# Sheet1.net
KiCad netlist of a schematic drawn in Altium Designer
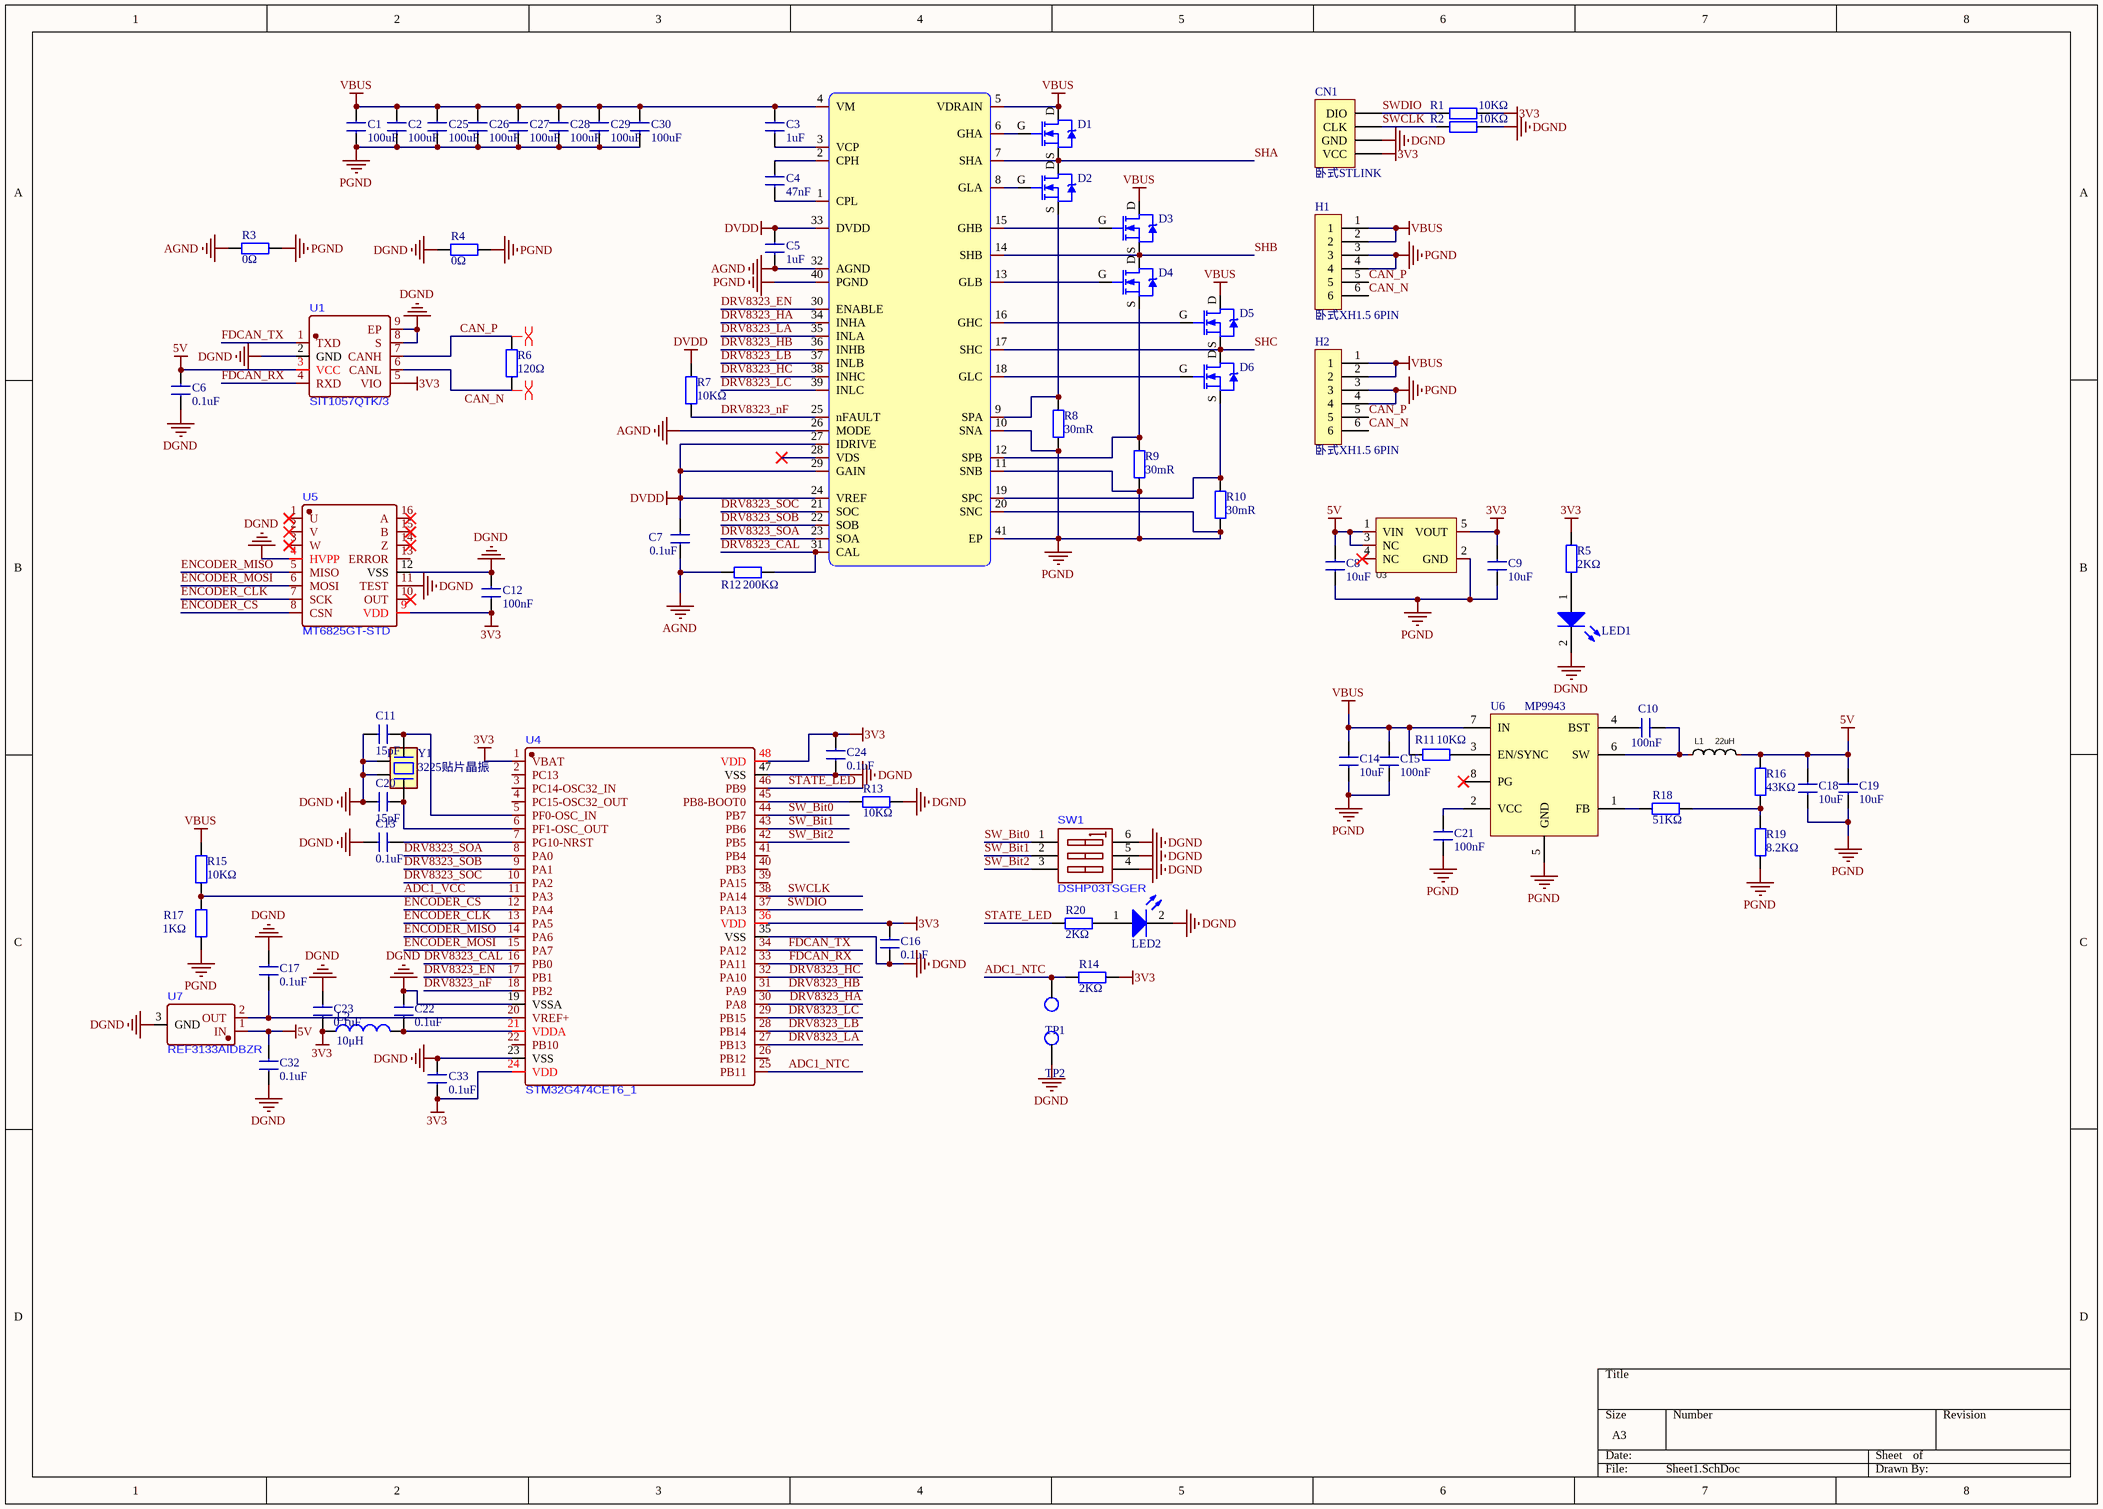
[diagram p0: Sheet1.SchDoc]

(export (version "E")
  (design (tool "Eeschema 10.0.6"))
  (components
    (comp (ref "C1")
      (value "100uF")
      (footprint "1206")
      (description "1210贴片电容")
      (libsource (lib "Integrated_Library1") (part "1210贴片电容"))
    )
    (comp (ref "C2")
      (value "100uF")
      (footprint "1206")
      (description "1210贴片电容")
      (libsource (lib "Integrated_Library1") (part "1210贴片电容"))
    )
    (comp (ref "C3")
      (value "1uF")
      (footprint "c0402")
      (description "贴片电容0402")
      (libsource (lib "Integrated_Library1") (part "0402贴片电容"))
    )
    (comp (ref "C4")
      (value "47nF")
      (footprint "c0402")
      (description "贴片电容0402")
      (libsource (lib "Integrated_Library1") (part "0402贴片电容"))
    )
    (comp (ref "C5")
      (value "1uF")
      (footprint "c0402")
      (description "贴片电容0402")
      (libsource (lib "Integrated_Library1") (part "0402贴片电容"))
    )
    (comp (ref "C6")
      (value "0.1uF")
      (footprint "c0402")
      (description "贴片电容0402")
      (libsource (lib "Integrated_Library1") (part "0402贴片电容"))
    )
    (comp (ref "C7")
      (value "0.1uF")
      (footprint "c0402")
      (description "贴片电容0402")
      (libsource (lib "Integrated_Library1") (part "0402贴片电容"))
    )
    (comp (ref "C8")
      (value "10uF")
      (footprint "c0402")
      (description "贴片电容0402")
      (libsource (lib "Integrated_Library1") (part "0402贴片电容"))
    )
    (comp (ref "C9")
      (value "10uF")
      (footprint "c0402")
      (description "贴片电容0402")
      (libsource (lib "Integrated_Library1") (part "0402贴片电容"))
    )
    (comp (ref "C10")
      (value "100nF")
      (footprint "c0402")
      (description "贴片电容0402")
      (libsource (lib "Integrated_Library1") (part "0402贴片电容"))
    )
    (comp (ref "C11")
      (value "15pF")
      (footprint "c0402")
      (description "贴片电容0402")
      (libsource (lib "Integrated_Library1") (part "0402贴片电容"))
    )
    (comp (ref "C12")
      (value "100nF")
      (footprint "C0402")
      (description "贴片电容0402")
      (libsource (lib "Integrated_Library1") (part "0402贴片电容"))
    )
    (comp (ref "C13")
      (value "0.1uF")
      (footprint "c0402")
      (description "贴片电容0402")
      (libsource (lib "Integrated_Library1") (part "0402贴片电容"))
    )
    (comp (ref "C14")
      (value "10uF")
      (footprint "C0603")
      (description "1210贴片电容")
      (libsource (lib "Integrated_Library1") (part "1210贴片电容"))
    )
    (comp (ref "C15")
      (value "100nF")
      (footprint "c0402")
      (description "贴片电容0402")
      (libsource (lib "Integrated_Library1") (part "0402贴片电容"))
    )
    (comp (ref "C16")
      (value "0.1uF")
      (footprint "c0402")
      (description "贴片电容0402")
      (libsource (lib "Integrated_Library1") (part "0402贴片电容"))
    )
    (comp (ref "C17")
      (value "0.1uF")
      (footprint "c0402")
      (description "贴片电容0402")
      (libsource (lib "Integrated_Library1") (part "0402贴片电容"))
    )
    (comp (ref "C18")
      (value "10uF")
      (footprint "C0603")
      (description "1210贴片电容")
      (libsource (lib "Integrated_Library1") (part "1210贴片电容"))
    )
    (comp (ref "C19")
      (value "10uF")
      (footprint "C0603")
      (description "1210贴片电容")
      (libsource (lib "Integrated_Library1") (part "1210贴片电容"))
    )
    (comp (ref "C20")
      (value "15pF")
      (footprint "c0402")
      (description "贴片电容0402")
      (libsource (lib "Integrated_Library1") (part "0402贴片电容"))
    )
    (comp (ref "C21")
      (value "100nF")
      (footprint "c0402")
      (description "贴片电容0402")
      (libsource (lib "Integrated_Library1") (part "0402贴片电容"))
    )
    (comp (ref "C22")
      (value "0.1uF")
      (footprint "c0402")
      (description "贴片电容0402")
      (libsource (lib "Integrated_Library1") (part "0402贴片电容"))
    )
    (comp (ref "C23")
      (value "0.1uF")
      (footprint "c0402")
      (description "贴片电容0402")
      (libsource (lib "Integrated_Library1") (part "0402贴片电容"))
    )
    (comp (ref "C24")
      (value "0.1uF")
      (footprint "c0402")
      (description "贴片电容0402")
      (libsource (lib "Integrated_Library1") (part "0402贴片电容"))
    )
    (comp (ref "C25")
      (value "100uF")
      (footprint "1206")
      (description "1210贴片电容")
      (libsource (lib "Integrated_Library1") (part "1210贴片电容"))
    )
    (comp (ref "C26")
      (value "100uF")
      (footprint "1206")
      (description "1210贴片电容")
      (libsource (lib "Integrated_Library1") (part "1210贴片电容"))
    )
    (comp (ref "C27")
      (value "100uF")
      (footprint "1206")
      (description "1210贴片电容")
      (libsource (lib "Integrated_Library1") (part "1210贴片电容"))
    )
    (comp (ref "C28")
      (value "100uF")
      (footprint "1206")
      (description "1210贴片电容")
      (libsource (lib "Integrated_Library1") (part "1210贴片电容"))
    )
    (comp (ref "C29")
      (value "100uF")
      (footprint "1206")
      (description "1210贴片电容")
      (libsource (lib "Integrated_Library1") (part "1210贴片电容"))
    )
    (comp (ref "C30")
      (value "100uF")
      (footprint "1206")
      (description "1210贴片电容")
      (libsource (lib "Integrated_Library1") (part "1210贴片电容"))
    )
    (comp (ref "C32")
      (value "0.1uF")
      (footprint "c0402")
      (description "贴片电容0402")
      (libsource (lib "Integrated_Library1") (part "0402贴片电容"))
    )
    (comp (ref "C33")
      (value "0.1uF")
      (footprint "c0402")
      (description "贴片电容0402")
      (libsource (lib "Integrated_Library1") (part "0402贴片电容"))
    )
    (comp (ref "CN1")
      (value "卧式STLINK")
      (footprint "CONN-SMD_4P-P1.25_GH1.25-4P")
      (libsource (lib "Integrated_Library1") (part "卧式STLINK"))
    )
    (comp (ref "D1")
      (value "NTMFS5C410NL")
      (footprint "DFN-8_L3.0-W3.0-P0.65-BL")
      (description "N沟道MOS管")
      (fields (field (name "PUBLISHER") "Altium Limited"))
      (libsource (lib "En") (part "NTMFS5C410NL"))
    )
    (comp (ref "D2")
      (value "NTMFS5C410NL")
      (footprint "DFN-8_L3.0-W3.0-P0.65-BL")
      (description "N沟道MOS管")
      (fields (field (name "PUBLISHER") "Altium Limited"))
      (libsource (lib "En") (part "NTMFS5C410NL"))
    )
    (comp (ref "D3")
      (value "NTMFS5C410NL")
      (footprint "DFN-8_L3.0-W3.0-P0.65-BL")
      (description "N沟道MOS管")
      (fields (field (name "PUBLISHER") "Altium Limited"))
      (libsource (lib "En") (part "NTMFS5C410NL"))
    )
    (comp (ref "D4")
      (value "NTMFS5C410NL")
      (footprint "DFN-8_L3.0-W3.0-P0.65-BL")
      (description "N沟道MOS管")
      (fields (field (name "PUBLISHER") "Altium Limited"))
      (libsource (lib "En") (part "NTMFS5C410NL"))
    )
    (comp (ref "D5")
      (value "NTMFS5C410NL")
      (footprint "DFN-8_L3.0-W3.0-P0.65-BL")
      (description "N沟道MOS管")
      (fields (field (name "PUBLISHER") "Altium Limited"))
      (libsource (lib "En") (part "NTMFS5C410NL"))
    )
    (comp (ref "D6")
      (value "NTMFS5C410NL")
      (footprint "DFN-8_L3.0-W3.0-P0.65-BL")
      (description "N沟道MOS管")
      (fields (field (name "PUBLISHER") "Altium Limited"))
      (libsource (lib "En") (part "NTMFS5C410NL"))
    )
    (comp (ref "H1")
      (value "卧式XH1.5 6PIN")
      (footprint "CONN-SMD_6P-P1.50_ZX-ZH1.5-6PWT")
      (libsource (lib "En") (part "卧式XH1.5 6PIN"))
    )
    (comp (ref "H2")
      (value "卧式XH1.5 6PIN")
      (footprint "CONN-SMD_6P-P1.50_ZX-ZH1.5-6PWT")
      (libsource (lib "En") (part "卧式XH1.5 6PIN"))
    )
    (comp (ref "L1")
      (value "22uH")
      (footprint "IND-SMD_L2.5-W2.0")
      (description "一体成型屏蔽电感，0530封装，额定电流3A")
      (fields (field (name "MANUFACTURER") "XR(祥如)") (field (name "MANUFACTURER PART") "XR0530-100M"))
      (libsource (lib "Integrated_Library1") (part "0530屏蔽电感"))
    )
    (comp (ref "L2")
      (value "10μH")
      (footprint "L0805")
      (description "0805贴片电感")
      (libsource (lib "Integrated_Library1") (part "0805贴片电感"))
    )
    (comp (ref "LED1")
      (value "LED")
      (footprint "led0805")
      (description "0805贴片LED")
      (libsource (lib "Integrated_Library1") (part "0805贴片LED"))
    )
    (comp (ref "LED2")
      (value "LED")
      (footprint "led0805")
      (description "0805贴片LED")
      (libsource (lib "Integrated_Library1") (part "0805贴片LED"))
    )
    (comp (ref "R1")
      (value "10KΩ")
      (footprint "R0402")
      (description "0402贴片电阻")
      (libsource (lib "") (part "0402贴片电阻_3"))
    )
    (comp (ref "R2")
      (value "10KΩ")
      (footprint "R0402")
      (description "0402贴片电阻")
      (libsource (lib "") (part "0402贴片电阻_3"))
    )
    (comp (ref "R3")
      (value "0Ω")
      (footprint "R0402")
      (description "0402贴片电阻")
      (libsource (lib "") (part "0402贴片电阻_3"))
    )
    (comp (ref "R4")
      (value "0Ω")
      (footprint "R0402")
      (description "0402贴片电阻")
      (libsource (lib "") (part "0402贴片电阻_3"))
    )
    (comp (ref "R5")
      (value "2KΩ")
      (footprint "R0402")
      (description "0402贴片电阻")
      (libsource (lib "") (part "0402贴片电阻_2"))
    )
    (comp (ref "R6")
      (value "120Ω")
      (footprint "R0402")
      (description "0402贴片电阻")
      (libsource (lib "") (part "0402贴片电阻_1"))
    )
    (comp (ref "R7")
      (value "10KΩ")
      (footprint "R0402")
      (description "0402贴片电阻")
      (libsource (lib "") (part "0402贴片电阻_2"))
    )
    (comp (ref "R8")
      (value "30mR")
      (footprint "1206")
      (description "2512检流电阻")
      (libsource (lib "Integrated_Library1") (part "2512检流电阻"))
    )
    (comp (ref "R9")
      (value "30mR")
      (footprint "1206")
      (description "2512检流电阻")
      (libsource (lib "Integrated_Library1") (part "2512检流电阻"))
    )
    (comp (ref "R10")
      (value "30mR")
      (footprint "1206")
      (description "2512检流电阻")
      (libsource (lib "Integrated_Library1") (part "2512检流电阻"))
    )
    (comp (ref "R11")
      (value "10KΩ")
      (footprint "R0402")
      (description "0402贴片电阻")
      (libsource (lib "Integrated_Library1") (part "0402贴片电阻"))
    )
    (comp (ref "R12")
      (value "200KΩ")
      (footprint "R0402")
      (description "0402贴片电阻")
      (libsource (lib "") (part "0402贴片电阻_5"))
    )
    (comp (ref "R13")
      (value "10KΩ")
      (footprint "R0402")
      (description "0402贴片电阻")
      (libsource (lib "") (part "0402贴片电阻_3"))
    )
    (comp (ref "R14")
      (value "2KΩ")
      (footprint "R0402")
      (description "0402贴片电阻")
      (libsource (lib "") (part "0402贴片电阻_3"))
    )
    (comp (ref "R15")
      (value "10KΩ")
      (footprint "R0402")
      (description "0402贴片电阻")
      (libsource (lib "") (part "0402贴片电阻_1"))
    )
    (comp (ref "R16")
      (value "43KΩ")
      (footprint "R0402")
      (description "0402贴片电阻")
      (libsource (lib "") (part "0402贴片电阻_4"))
    )
    (comp (ref "R17")
      (value "1KΩ")
      (footprint "R0402")
      (description "0402贴片电阻")
      (libsource (lib "") (part "0402贴片电阻_2"))
    )
    (comp (ref "R18")
      (value "51KΩ")
      (footprint "R0402")
      (description "0402贴片电阻")
      (libsource (lib "Integrated_Library1") (part "0402贴片电阻"))
    )
    (comp (ref "R19")
      (value "8.2KΩ")
      (footprint "R0402")
      (description "0402贴片电阻")
      (libsource (lib "") (part "0402贴片电阻_4"))
    )
    (comp (ref "R20")
      (value "2KΩ")
      (footprint "R0402")
      (description "0402贴片电阻")
      (libsource (lib "") (part "0402贴片电阻_3"))
    )
    (comp (ref "SW1")
      (value "DSHP03TSGER")
      (footprint "SW-SMD_6P-L5.4-W5.4-P1.27-LS8.4")
      (libsource (lib "Integrated_Library1") (part "DSHP03TSGER"))
    )
    (comp (ref "TP1")
      (value "testpoint")
      (footprint "testpoint")
      (libsource (lib "Integrated_Library1") (part "testpoint"))
    )
    (comp (ref "TP2")
      (value "testpoint")
      (footprint "testpoint")
      (libsource (lib "Integrated_Library1") (part "testpoint"))
    )
    (comp (ref "U1")
      (value "SIT1057QTK/3")
      (footprint "DFN-8_L3.0-W3.0-P0.65-BL-EP")
      (libsource (lib "En") (part "SIT1057QTK/3"))
    )
    (comp (ref "U2")
      (value "DRV8323HRTAR")
      (footprint "QFN-40_L6.0-W6.0-P0.50-BL-EP4.5")
      (fields (field (name "MANUFACTURER") "TI(德州仪器)"))
      (libsource (lib "Integrated_Library1") (part "DRV8323HRTAR"))
    )
    (comp (ref "U3")
      (value "XC6201P332MR-HXY")
      (footprint "SOT-23-5_L3.0-W1.7-P0.95-LS2.8-BR")
      (description "3.3V LDO")
      (fields (field (name "MANUFACTURER") "HXY MOSFET(华轩阳电子)"))
      (libsource (lib "Integrated_Library1") (part "XC6201P332MR-HXY"))
    )
    (comp (ref "U4")
      (value "STM32G474CET6_1")
      (footprint "LQFP-48_L7.0-W7.0-P0.50-LS9.0-BL")
      (libsource (lib "Integrated_Library1") (part "STM32G474CET6_1"))
    )
    (comp (ref "U5")
      (value "MT6825GT-STD")
      (footprint "TSSOP-16_L5.0-W4.4-P0.65-LS6.4-BL-1")
      (description "18位绝对角编码器")
      (libsource (lib "Integrated_Library1") (part "MT6825GT-STD"))
    )
    (comp (ref "U6")
      (value "MP9943")
      (footprint "QFN-8 3x3")
      (libsource (lib "Integrated_Library1") (part "MP9943"))
    )
    (comp (ref "U7")
      (value "REF3133AIDBZR")
      (footprint "SOT-23-3_L2.9-W1.3-P1.90-LS2.4-BR")
      (libsource (lib "Integrated_Library1") (part "REF3133AIDBZR"))
    )
    (comp (ref "Y1")
      (value "3225贴片晶振")
      (footprint "OSC-3225-4P")
      (libsource (lib "Integrated_Library1") (part "3225贴片晶振"))
    )
  )
  (nets
    (net (code "1") (name "/ADC1_NTC") (class "Default")
      (node (ref "R14") (pin "1") (pinfunction "1_1") (pintype "passive"))
      (node (ref "TP1") (pin "1") (pinfunction "1_1") (pintype "passive"))
      (node (ref "U4") (pin "25") (pinfunction "PB11_25") (pintype "passive"))
    )
    (net (code "2") (name "/ADC1_VCC") (class "Default")
      (node (ref "R15") (pin "1") (pinfunction "1_1") (pintype "passive"))
      (node (ref "R17") (pin "1") (pinfunction "1_1") (pintype "passive"))
      (node (ref "U4") (pin "11") (pinfunction "PA3_11") (pintype "passive"))
    )
    (net (code "3") (name "/CAN_N") (class "Default")
      (node (ref "H1") (pin "6") (pinfunction "6_6") (pintype "passive"))
      (node (ref "H2") (pin "6") (pinfunction "6_6") (pintype "passive"))
      (node (ref "R6") (pin "1") (pinfunction "1_1") (pintype "passive"))
      (node (ref "U1") (pin "6") (pinfunction "CANL_6") (pintype "passive"))
    )
    (net (code "4") (name "/CAN_P") (class "Default")
      (node (ref "H1") (pin "5") (pinfunction "5_5") (pintype "passive"))
      (node (ref "H2") (pin "5") (pinfunction "5_5") (pintype "passive"))
      (node (ref "R6") (pin "2") (pinfunction "2_2") (pintype "passive"))
      (node (ref "U1") (pin "7") (pinfunction "CANH_7") (pintype "passive"))
    )
    (net (code "5") (name "/DRV8323_CAL") (class "Default")
      (node (ref "R12") (pin "1") (pinfunction "1_1") (pintype "passive"))
      (node (ref "U2") (pin "31") (pinfunction "CAL_31") (pintype "passive"))
      (node (ref "U4") (pin "16") (pinfunction "PB0_16") (pintype "passive"))
    )
    (net (code "6") (name "/DRV8323_EN") (class "Default")
      (node (ref "U2") (pin "30") (pinfunction "ENABLE_30") (pintype "passive"))
      (node (ref "U4") (pin "17") (pinfunction "PB1_17") (pintype "passive"))
    )
    (net (code "7") (name "/DRV8323_HA") (class "Default")
      (node (ref "U2") (pin "34") (pinfunction "INHA_34") (pintype "passive"))
      (node (ref "U4") (pin "30") (pinfunction "PA8_30") (pintype "passive"))
    )
    (net (code "8") (name "/DRV8323_HB") (class "Default")
      (node (ref "U2") (pin "36") (pinfunction "INHB_36") (pintype "passive"))
      (node (ref "U4") (pin "31") (pinfunction "PA9_31") (pintype "passive"))
    )
    (net (code "9") (name "/DRV8323_HC") (class "Default")
      (node (ref "U2") (pin "38") (pinfunction "INHC_38") (pintype "passive"))
      (node (ref "U4") (pin "32") (pinfunction "PA10_32") (pintype "passive"))
    )
    (net (code "10") (name "/DRV8323_LA") (class "Default")
      (node (ref "U2") (pin "35") (pinfunction "INLA_35") (pintype "passive"))
      (node (ref "U4") (pin "27") (pinfunction "PB13_27") (pintype "passive"))
    )
    (net (code "11") (name "/DRV8323_LB") (class "Default")
      (node (ref "U2") (pin "37") (pinfunction "INLB_37") (pintype "passive"))
      (node (ref "U4") (pin "28") (pinfunction "PB14_28") (pintype "passive"))
    )
    (net (code "12") (name "/DRV8323_LC") (class "Default")
      (node (ref "U2") (pin "39") (pinfunction "INLC_39") (pintype "passive"))
      (node (ref "U4") (pin "29") (pinfunction "PB15_29") (pintype "passive"))
    )
    (net (code "13") (name "/DRV8323_SOA") (class "Default")
      (node (ref "U2") (pin "23") (pinfunction "SOA_23") (pintype "passive"))
      (node (ref "U4") (pin "8") (pinfunction "PA0_8") (pintype "passive"))
    )
    (net (code "14") (name "/DRV8323_SOB") (class "Default")
      (node (ref "U2") (pin "22") (pinfunction "SOB_22") (pintype "passive"))
      (node (ref "U4") (pin "9") (pinfunction "PA1_9") (pintype "passive"))
    )
    (net (code "15") (name "/DRV8323_SOC") (class "Default")
      (node (ref "U2") (pin "21") (pinfunction "SOC_21") (pintype "passive"))
      (node (ref "U4") (pin "10") (pinfunction "PA2_10") (pintype "passive"))
    )
    (net (code "16") (name "/DRV8323_nF") (class "Default")
      (node (ref "R7") (pin "2") (pinfunction "2_2") (pintype "passive"))
      (node (ref "U2") (pin "25") (pinfunction "nFAULT_25") (pintype "passive"))
      (node (ref "U4") (pin "18") (pinfunction "PB2_18") (pintype "passive"))
    )
    (net (code "17") (name "/ENCODER_CLK") (class "Default")
      (node (ref "U4") (pin "13") (pinfunction "PA5_13") (pintype "passive"))
      (node (ref "U5") (pin "7") (pinfunction "SCK_7") (pintype "passive"))
    )
    (net (code "18") (name "/ENCODER_CS") (class "Default")
      (node (ref "U4") (pin "12") (pinfunction "PA4_12") (pintype "passive"))
      (node (ref "U5") (pin "8") (pinfunction "CSN_8") (pintype "passive"))
    )
    (net (code "19") (name "/ENCODER_MISO") (class "Default")
      (node (ref "U4") (pin "14") (pinfunction "PA6_14") (pintype "passive"))
      (node (ref "U5") (pin "5") (pinfunction "MISO_5") (pintype "passive"))
    )
    (net (code "20") (name "/ENCODER_MOSI") (class "Default")
      (node (ref "U4") (pin "15") (pinfunction "PA7_15") (pintype "passive"))
      (node (ref "U5") (pin "6") (pinfunction "MOSI_6") (pintype "passive"))
    )
    (net (code "21") (name "/FDCAN_RX") (class "Default")
      (node (ref "U1") (pin "4") (pinfunction "RXD_4") (pintype "passive"))
      (node (ref "U4") (pin "33") (pinfunction "PA11_33") (pintype "passive"))
    )
    (net (code "22") (name "/FDCAN_TX") (class "Default")
      (node (ref "U1") (pin "1") (pinfunction "TXD_1") (pintype "passive"))
      (node (ref "U4") (pin "34") (pinfunction "PA12_34") (pintype "passive"))
    )
    (net (code "23") (name "/SHA") (class "Default")
      (node (ref "D1") (pin "S") (pinfunction "S_S") (pintype "passive"))
      (node (ref "D2") (pin "D") (pinfunction "D_D") (pintype "passive"))
      (node (ref "U2") (pin "7") (pinfunction "SHA_7") (pintype "passive"))
    )
    (net (code "24") (name "/SHB") (class "Default")
      (node (ref "D3") (pin "S") (pinfunction "S_S") (pintype "passive"))
      (node (ref "D4") (pin "D") (pinfunction "D_D") (pintype "passive"))
      (node (ref "U2") (pin "14") (pinfunction "SHB_14") (pintype "passive"))
    )
    (net (code "25") (name "/SHC") (class "Default")
      (node (ref "D5") (pin "S") (pinfunction "S_S") (pintype "passive"))
      (node (ref "D6") (pin "D") (pinfunction "D_D") (pintype "passive"))
      (node (ref "U2") (pin "17") (pinfunction "SHC_17") (pintype "passive"))
    )
    (net (code "26") (name "/STATE_LED") (class "Default")
      (node (ref "R20") (pin "1") (pinfunction "1_1") (pintype "passive"))
      (node (ref "U4") (pin "46") (pinfunction "PB9_46") (pintype "passive"))
    )
    (net (code "27") (name "/SWCLK") (class "Default")
      (node (ref "CN1") (pin "3") (pinfunction "CLK_3") (pintype "passive"))
      (node (ref "R2") (pin "1") (pinfunction "1_1") (pintype "passive"))
      (node (ref "U4") (pin "38") (pinfunction "PA14_38") (pintype "passive"))
    )
    (net (code "28") (name "/SWDIO") (class "Default")
      (node (ref "CN1") (pin "4") (pinfunction "DIO_4") (pintype "passive"))
      (node (ref "R1") (pin "1") (pinfunction "1_1") (pintype "passive"))
      (node (ref "U4") (pin "37") (pinfunction "PA13_37") (pintype "passive"))
    )
    (net (code "29") (name "/SW_Bit0") (class "Default")
      (node (ref "SW1") (pin "1") (pinfunction "A1_1") (pintype "passive"))
      (node (ref "U4") (pin "44") (pinfunction "PB7_44") (pintype "passive"))
    )
    (net (code "30") (name "/SW_Bit1") (class "Default")
      (node (ref "SW1") (pin "2") (pinfunction "A2_2") (pintype "passive"))
      (node (ref "U4") (pin "43") (pinfunction "PB6_43") (pintype "passive"))
    )
    (net (code "31") (name "/SW_Bit2") (class "Default")
      (node (ref "SW1") (pin "3") (pinfunction "A3_3") (pintype "passive"))
      (node (ref "U4") (pin "42") (pinfunction "PB5_42") (pintype "passive"))
    )
    (net (code "32") (name "3V3") (class "Default")
      (node (ref "C12") (pin "1") (pinfunction "1_1") (pintype "passive"))
      (node (ref "C16") (pin "1") (pinfunction "1_1") (pintype "passive"))
      (node (ref "C23") (pin "2") (pinfunction "2_2") (pintype "passive"))
      (node (ref "C24") (pin "1") (pinfunction "1_1") (pintype "passive"))
      (node (ref "C33") (pin "2") (pinfunction "2_2") (pintype "passive"))
      (node (ref "C9") (pin "2") (pinfunction "2_2") (pintype "passive"))
      (node (ref "CN1") (pin "1") (pinfunction "VCC_1") (pintype "passive"))
      (node (ref "L2") (pin "1") (pinfunction "1_1") (pintype "passive"))
      (node (ref "R1") (pin "2") (pinfunction "2_2") (pintype "passive"))
      (node (ref "R14") (pin "2") (pinfunction "2_2") (pintype "passive"))
      (node (ref "R5") (pin "1") (pinfunction "1_1") (pintype "passive"))
      (node (ref "U1") (pin "5") (pinfunction "VIO_5") (pintype "passive"))
      (node (ref "U3") (pin "5") (pinfunction "VOUT_5") (pintype "passive"))
      (node (ref "U4") (pin "1") (pinfunction "VBAT_1") (pintype "passive"))
      (node (ref "U4") (pin "24") (pinfunction "VDD_24") (pintype "passive"))
      (node (ref "U4") (pin "36") (pinfunction "VDD_36") (pintype "passive"))
      (node (ref "U4") (pin "48") (pinfunction "VDD_48") (pintype "passive"))
      (node (ref "U5") (pin "9") (pinfunction "VDD_9") (pintype "passive"))
    )
    (net (code "33") (name "5V") (class "Default")
      (node (ref "C18") (pin "2") (pinfunction "2_2") (pintype "passive"))
      (node (ref "C19") (pin "2") (pinfunction "2_2") (pintype "passive"))
      (node (ref "C32") (pin "1") (pinfunction "1_1") (pintype "passive"))
      (node (ref "C6") (pin "2") (pinfunction "2_2") (pintype "passive"))
      (node (ref "C8") (pin "2") (pinfunction "2_2") (pintype "passive"))
      (node (ref "L1") (pin "2") (pinfunction "2_2") (pintype "passive"))
      (node (ref "R16") (pin "2") (pinfunction "2_2") (pintype "passive"))
      (node (ref "U1") (pin "3") (pinfunction "VCC_3") (pintype "passive"))
      (node (ref "U3") (pin "1") (pinfunction "VIN_1") (pintype "passive"))
      (node (ref "U3") (pin "3") (pinfunction "NC_3") (pintype "passive"))
      (node (ref "U7") (pin "1") (pinfunction "IN_1") (pintype "passive"))
    )
    (net (code "34") (name "AGND") (class "Default")
      (node (ref "C5") (pin "1") (pinfunction "1_1") (pintype "passive"))
      (node (ref "C7") (pin "1") (pinfunction "1_1") (pintype "passive"))
      (node (ref "R12") (pin "2") (pinfunction "2_2") (pintype "passive"))
      (node (ref "R3") (pin "1") (pinfunction "1_1") (pintype "passive"))
      (node (ref "U2") (pin "26") (pinfunction "MODE_26") (pintype "passive"))
      (node (ref "U2") (pin "32") (pinfunction "AGND_32") (pintype "passive"))
    )
    (net (code "35") (name "DGND") (class "Default")
      (node (ref "C11") (pin "2") (pinfunction "2_2") (pintype "passive"))
      (node (ref "C12") (pin "2") (pinfunction "2_2") (pintype "passive"))
      (node (ref "C13") (pin "2") (pinfunction "2_2") (pintype "passive"))
      (node (ref "C16") (pin "2") (pinfunction "2_2") (pintype "passive"))
      (node (ref "C17") (pin "2") (pinfunction "2_2") (pintype "passive"))
      (node (ref "C20") (pin "2") (pinfunction "2_2") (pintype "passive"))
      (node (ref "C22") (pin "1") (pinfunction "1_1") (pintype "passive"))
      (node (ref "C23") (pin "1") (pinfunction "1_1") (pintype "passive"))
      (node (ref "C24") (pin "2") (pinfunction "2_2") (pintype "passive"))
      (node (ref "C32") (pin "2") (pinfunction "2_2") (pintype "passive"))
      (node (ref "C33") (pin "1") (pinfunction "1_1") (pintype "passive"))
      (node (ref "C6") (pin "1") (pinfunction "1_1") (pintype "passive"))
      (node (ref "CN1") (pin "2") (pinfunction "GND_2") (pintype "passive"))
      (node (ref "LED1") (pin "2") (pinfunction "K_2") (pintype "passive"))
      (node (ref "LED2") (pin "2") (pinfunction "K_2") (pintype "passive"))
      (node (ref "R13") (pin "2") (pinfunction "2_2") (pintype "passive"))
      (node (ref "R2") (pin "2") (pinfunction "2_2") (pintype "passive"))
      (node (ref "R4") (pin "1") (pinfunction "1_1") (pintype "passive"))
      (node (ref "SW1") (pin "4") (pinfunction "B3_4") (pintype "passive"))
      (node (ref "SW1") (pin "5") (pinfunction "B2_5") (pintype "passive"))
      (node (ref "SW1") (pin "6") (pinfunction "B1_6") (pintype "passive"))
      (node (ref "TP2") (pin "1") (pinfunction "1_1") (pintype "passive"))
      (node (ref "U1") (pin "2") (pinfunction "GND_2") (pintype "passive"))
      (node (ref "U1") (pin "8") (pinfunction "S_8") (pintype "passive"))
      (node (ref "U1") (pin "9") (pinfunction "EP_9") (pintype "passive"))
      (node (ref "U4") (pin "19") (pinfunction "VSSA_19") (pintype "passive"))
      (node (ref "U4") (pin "23") (pinfunction "VSS_23") (pintype "passive"))
      (node (ref "U4") (pin "35") (pinfunction "VSS_35") (pintype "passive"))
      (node (ref "U4") (pin "47") (pinfunction "VSS_47") (pintype "passive"))
      (node (ref "U5") (pin "11") (pinfunction "TEST_11") (pintype "passive"))
      (node (ref "U5") (pin "12") (pinfunction "VSS_12") (pintype "passive"))
      (node (ref "U5") (pin "4") (pinfunction "HVPP_4") (pintype "passive"))
      (node (ref "U7") (pin "3") (pinfunction "GND_3") (pintype "passive"))
      (node (ref "Y1") (pin "2") (pinfunction "2_2") (pintype "passive"))
      (node (ref "Y1") (pin "4") (pinfunction "4_4") (pintype "passive"))
    )
    (net (code "36") (name "DVDD") (class "Default")
      (node (ref "C5") (pin "2") (pinfunction "2_2") (pintype "passive"))
      (node (ref "C7") (pin "2") (pinfunction "2_2") (pintype "passive"))
      (node (ref "R7") (pin "1") (pinfunction "1_1") (pintype "passive"))
      (node (ref "U2") (pin "24") (pinfunction "VREF_24") (pintype "passive"))
      (node (ref "U2") (pin "27") (pinfunction "IDRIVE_27") (pintype "passive"))
      (node (ref "U2") (pin "29") (pinfunction "GAIN_29") (pintype "passive"))
      (node (ref "U2") (pin "33") (pinfunction "DVDD_33") (pintype "passive"))
    )
    (net (code "37") (name "Net-(LED1-A)") (class "Default")
      (node (ref "LED1") (pin "1") (pinfunction "A_1") (pintype "passive"))
      (node (ref "R5") (pin "2") (pinfunction "2_2") (pintype "passive"))
    )
    (net (code "38") (name "Net-(LED2-A)") (class "Default")
      (node (ref "LED2") (pin "1") (pinfunction "A_1") (pintype "passive"))
      (node (ref "R20") (pin "2") (pinfunction "2_2") (pintype "passive"))
    )
    (net (code "39") (name "Net-(R16-Pad1)") (class "Default")
      (node (ref "R16") (pin "1") (pinfunction "1_1") (pintype "passive"))
      (node (ref "R18") (pin "2") (pinfunction "2_2") (pintype "passive"))
      (node (ref "R19") (pin "2") (pinfunction "2_2") (pintype "passive"))
    )
    (net (code "40") (name "Net-(U2-CPH)") (class "Default")
      (node (ref "C4") (pin "2") (pinfunction "2_2") (pintype "passive"))
      (node (ref "U2") (pin "2") (pinfunction "CPH_2") (pintype "passive"))
    )
    (net (code "41") (name "Net-(U2-CPL)") (class "Default")
      (node (ref "C4") (pin "1") (pinfunction "1_1") (pintype "passive"))
      (node (ref "U2") (pin "1") (pinfunction "CPL_1") (pintype "passive"))
    )
    (net (code "42") (name "Net-(U2-GHA)") (class "Default")
      (node (ref "D1") (pin "G") (pinfunction "G_G") (pintype "passive"))
      (node (ref "U2") (pin "6") (pinfunction "GHA_6") (pintype "passive"))
    )
    (net (code "43") (name "Net-(U2-GHB)") (class "Default")
      (node (ref "D3") (pin "G") (pinfunction "G_G") (pintype "passive"))
      (node (ref "U2") (pin "15") (pinfunction "GHB_15") (pintype "passive"))
    )
    (net (code "44") (name "Net-(U2-GHC)") (class "Default")
      (node (ref "D5") (pin "G") (pinfunction "G_G") (pintype "passive"))
      (node (ref "U2") (pin "16") (pinfunction "GHC_16") (pintype "passive"))
    )
    (net (code "45") (name "Net-(U2-GLA)") (class "Default")
      (node (ref "D2") (pin "G") (pinfunction "G_G") (pintype "passive"))
      (node (ref "U2") (pin "8") (pinfunction "GLA_8") (pintype "passive"))
    )
    (net (code "46") (name "Net-(U2-GLB)") (class "Default")
      (node (ref "D4") (pin "G") (pinfunction "G_G") (pintype "passive"))
      (node (ref "U2") (pin "13") (pinfunction "GLB_13") (pintype "passive"))
    )
    (net (code "47") (name "Net-(U2-GLC)") (class "Default")
      (node (ref "D6") (pin "G") (pinfunction "G_G") (pintype "passive"))
      (node (ref "U2") (pin "18") (pinfunction "GLC_18") (pintype "passive"))
    )
    (net (code "48") (name "Net-(U2-SPA)") (class "Default")
      (node (ref "D2") (pin "S") (pinfunction "S_S") (pintype "passive"))
      (node (ref "R8") (pin "2") (pinfunction "2_2") (pintype "passive"))
      (node (ref "U2") (pin "9") (pinfunction "SPA_9") (pintype "passive"))
    )
    (net (code "49") (name "Net-(U2-SPB)") (class "Default")
      (node (ref "D4") (pin "S") (pinfunction "S_S") (pintype "passive"))
      (node (ref "R9") (pin "2") (pinfunction "2_2") (pintype "passive"))
      (node (ref "U2") (pin "12") (pinfunction "SPB_12") (pintype "passive"))
    )
    (net (code "50") (name "Net-(U2-SPC)") (class "Default")
      (node (ref "D6") (pin "S") (pinfunction "S_S") (pintype "passive"))
      (node (ref "R10") (pin "2") (pinfunction "2_2") (pintype "passive"))
      (node (ref "U2") (pin "19") (pinfunction "SPC_19") (pintype "passive"))
    )
    (net (code "51") (name "Net-(U2-VCP)") (class "Default")
      (node (ref "C3") (pin "1") (pinfunction "1_1") (pintype "passive"))
      (node (ref "U2") (pin "3") (pinfunction "VCP_3") (pintype "passive"))
    )
    (net (code "52") (name "Net-(U4-PB8-BOOT0)") (class "Default")
      (node (ref "R13") (pin "1") (pinfunction "1_1") (pintype "passive"))
      (node (ref "U4") (pin "45") (pinfunction "PB8-BOOT0_45") (pintype "passive"))
    )
    (net (code "53") (name "Net-(U4-PF0-OSC_IN)") (class "Default")
      (node (ref "C11") (pin "1") (pinfunction "1_1") (pintype "passive"))
      (node (ref "U4") (pin "5") (pinfunction "PF0-OSC_IN_5") (pintype "passive"))
      (node (ref "Y1") (pin "3") (pinfunction "3_3") (pintype "passive"))
    )
    (net (code "54") (name "Net-(U4-PF1-OSC_OUT)") (class "Default")
      (node (ref "C20") (pin "1") (pinfunction "1_1") (pintype "passive"))
      (node (ref "U4") (pin "6") (pinfunction "PF1-OSC_OUT_6") (pintype "passive"))
      (node (ref "Y1") (pin "1") (pinfunction "1_1") (pintype "passive"))
    )
    (net (code "55") (name "Net-(U4-PG10-NRST)") (class "Default")
      (node (ref "C13") (pin "1") (pinfunction "1_1") (pintype "passive"))
      (node (ref "U4") (pin "7") (pinfunction "PG10-NRST_7") (pintype "passive"))
    )
    (net (code "56") (name "Net-(U4-VDDA)") (class "Default")
      (node (ref "C22") (pin "2") (pinfunction "2_2") (pintype "passive"))
      (node (ref "L2") (pin "2") (pinfunction "2_2") (pintype "passive"))
      (node (ref "U4") (pin "21") (pinfunction "VDDA_21") (pintype "passive"))
    )
    (net (code "57") (name "Net-(U4-VREF+)") (class "Default")
      (node (ref "C17") (pin "1") (pinfunction "1_1") (pintype "passive"))
      (node (ref "U4") (pin "20") (pinfunction "VREF+_20") (pintype "passive"))
      (node (ref "U7") (pin "2") (pinfunction "OUT_2") (pintype "passive"))
    )
    (net (code "58") (name "Net-(U6-BST)") (class "Default")
      (node (ref "C10") (pin "1") (pinfunction "1_1") (pintype "passive"))
      (node (ref "U6") (pin "4") (pinfunction "BST_4") (pintype "passive"))
    )
    (net (code "59") (name "Net-(U6-EN{slash}SYNC)") (class "Default")
      (node (ref "R11") (pin "2") (pinfunction "2_2") (pintype "passive"))
      (node (ref "U6") (pin "3") (pinfunction "EN/SYNC_3") (pintype "passive"))
    )
    (net (code "60") (name "Net-(U6-FB)") (class "Default")
      (node (ref "R18") (pin "1") (pinfunction "1_1") (pintype "passive"))
      (node (ref "U6") (pin "1") (pinfunction "FB_1") (pintype "passive"))
    )
    (net (code "61") (name "Net-(U6-SW)") (class "Default")
      (node (ref "C10") (pin "2") (pinfunction "2_2") (pintype "passive"))
      (node (ref "L1") (pin "1") (pinfunction "1_1") (pintype "passive"))
      (node (ref "U6") (pin "6") (pinfunction "SW_6") (pintype "passive"))
    )
    (net (code "62") (name "Net-(U6-VCC)") (class "Default")
      (node (ref "C21") (pin "2") (pinfunction "2_2") (pintype "passive"))
      (node (ref "U6") (pin "2") (pinfunction "VCC_2") (pintype "passive"))
    )
    (net (code "63") (name "PGND") (class "Default")
      (node (ref "C1") (pin "1") (pinfunction "1_1") (pintype "passive"))
      (node (ref "C14") (pin "1") (pinfunction "1_1") (pintype "passive"))
      (node (ref "C15") (pin "1") (pinfunction "1_1") (pintype "passive"))
      (node (ref "C18") (pin "1") (pinfunction "1_1") (pintype "passive"))
      (node (ref "C19") (pin "1") (pinfunction "1_1") (pintype "passive"))
      (node (ref "C2") (pin "1") (pinfunction "1_1") (pintype "passive"))
      (node (ref "C21") (pin "1") (pinfunction "1_1") (pintype "passive"))
      (node (ref "C25") (pin "1") (pinfunction "1_1") (pintype "passive"))
      (node (ref "C26") (pin "1") (pinfunction "1_1") (pintype "passive"))
      (node (ref "C27") (pin "1") (pinfunction "1_1") (pintype "passive"))
      (node (ref "C28") (pin "1") (pinfunction "1_1") (pintype "passive"))
      (node (ref "C29") (pin "1") (pinfunction "1_1") (pintype "passive"))
      (node (ref "C30") (pin "1") (pinfunction "1_1") (pintype "passive"))
      (node (ref "C8") (pin "1") (pinfunction "1_1") (pintype "passive"))
      (node (ref "C9") (pin "1") (pinfunction "1_1") (pintype "passive"))
      (node (ref "H1") (pin "3") (pinfunction "3_3") (pintype "passive"))
      (node (ref "H1") (pin "4") (pinfunction "4_4") (pintype "passive"))
      (node (ref "H2") (pin "3") (pinfunction "3_3") (pintype "passive"))
      (node (ref "H2") (pin "4") (pinfunction "4_4") (pintype "passive"))
      (node (ref "R10") (pin "1") (pinfunction "1_1") (pintype "passive"))
      (node (ref "R17") (pin "2") (pinfunction "2_2") (pintype "passive"))
      (node (ref "R19") (pin "1") (pinfunction "1_1") (pintype "passive"))
      (node (ref "R3") (pin "2") (pinfunction "2_2") (pintype "passive"))
      (node (ref "R4") (pin "2") (pinfunction "2_2") (pintype "passive"))
      (node (ref "R8") (pin "1") (pinfunction "1_1") (pintype "passive"))
      (node (ref "R9") (pin "1") (pinfunction "1_1") (pintype "passive"))
      (node (ref "U2") (pin "10") (pinfunction "SNA_10") (pintype "passive"))
      (node (ref "U2") (pin "11") (pinfunction "SNB_11") (pintype "passive"))
      (node (ref "U2") (pin "20") (pinfunction "SNC_20") (pintype "passive"))
      (node (ref "U2") (pin "40") (pinfunction "PGND_40") (pintype "passive"))
      (node (ref "U2") (pin "41") (pinfunction "EP_41") (pintype "passive"))
      (node (ref "U3") (pin "2") (pinfunction "GND_2") (pintype "passive"))
      (node (ref "U6") (pin "5") (pinfunction "GND_5") (pintype "passive"))
    )
    (net (code "64") (name "VBUS") (class "Default")
      (node (ref "C1") (pin "2") (pinfunction "2_2") (pintype "passive"))
      (node (ref "C14") (pin "2") (pinfunction "2_2") (pintype "passive"))
      (node (ref "C15") (pin "2") (pinfunction "2_2") (pintype "passive"))
      (node (ref "C2") (pin "2") (pinfunction "2_2") (pintype "passive"))
      (node (ref "C25") (pin "2") (pinfunction "2_2") (pintype "passive"))
      (node (ref "C26") (pin "2") (pinfunction "2_2") (pintype "passive"))
      (node (ref "C27") (pin "2") (pinfunction "2_2") (pintype "passive"))
      (node (ref "C28") (pin "2") (pinfunction "2_2") (pintype "passive"))
      (node (ref "C29") (pin "2") (pinfunction "2_2") (pintype "passive"))
      (node (ref "C3") (pin "2") (pinfunction "2_2") (pintype "passive"))
      (node (ref "C30") (pin "2") (pinfunction "2_2") (pintype "passive"))
      (node (ref "D1") (pin "D") (pinfunction "D_D") (pintype "passive"))
      (node (ref "D3") (pin "D") (pinfunction "D_D") (pintype "passive"))
      (node (ref "D5") (pin "D") (pinfunction "D_D") (pintype "passive"))
      (node (ref "H1") (pin "1") (pinfunction "1_1") (pintype "passive"))
      (node (ref "H1") (pin "2") (pinfunction "2_2") (pintype "passive"))
      (node (ref "H2") (pin "1") (pinfunction "1_1") (pintype "passive"))
      (node (ref "H2") (pin "2") (pinfunction "2_2") (pintype "passive"))
      (node (ref "R11") (pin "1") (pinfunction "1_1") (pintype "passive"))
      (node (ref "R15") (pin "2") (pinfunction "2_2") (pintype "passive"))
      (node (ref "U2") (pin "4") (pinfunction "VM_4") (pintype "passive"))
      (node (ref "U2") (pin "5") (pinfunction "VDRAIN_5") (pintype "passive"))
      (node (ref "U6") (pin "7") (pinfunction "IN_7") (pintype "passive"))
    )
    (net (code "65") (name "unconnected-(U2-VDS-Pad28)") (class "Default")
      (node (ref "U2") (pin "28") (pinfunction "VDS_28") (pintype "passive+no_connect"))
    )
    (net (code "66") (name "unconnected-(U3-NC-Pad4)") (class "Default")
      (node (ref "U3") (pin "4") (pinfunction "NC_4") (pintype "passive+no_connect"))
    )
    (net (code "67") (name "unconnected-(U4-PA15-Pad39)") (class "Default")
      (node (ref "U4") (pin "39") (pinfunction "PA15_39") (pintype "passive"))
    )
    (net (code "68") (name "unconnected-(U4-PB3-Pad40)") (class "Default")
      (node (ref "U4") (pin "40") (pinfunction "PB3_40") (pintype "passive"))
    )
    (net (code "69") (name "unconnected-(U4-PB4-Pad41)") (class "Default")
      (node (ref "U4") (pin "41") (pinfunction "PB4_41") (pintype "passive"))
    )
    (net (code "70") (name "unconnected-(U4-PB10-Pad22)") (class "Default")
      (node (ref "U4") (pin "22") (pinfunction "PB10_22") (pintype "passive"))
    )
    (net (code "71") (name "unconnected-(U4-PB12-Pad26)") (class "Default")
      (node (ref "U4") (pin "26") (pinfunction "PB12_26") (pintype "passive"))
    )
    (net (code "72") (name "unconnected-(U4-PC13-Pad2)") (class "Default")
      (node (ref "U4") (pin "2") (pinfunction "PC13_2") (pintype "passive"))
    )
    (net (code "73") (name "unconnected-(U4-PC14-OSC32_IN-Pad3)") (class "Default")
      (node (ref "U4") (pin "3") (pinfunction "PC14-OSC32_IN_3") (pintype "passive"))
    )
    (net (code "74") (name "unconnected-(U4-PC15-OSC32_OUT-Pad4)") (class "Default")
      (node (ref "U4") (pin "4") (pinfunction "PC15-OSC32_OUT_4") (pintype "passive"))
    )
    (net (code "75") (name "unconnected-(U5-A-Pad16)") (class "Default")
      (node (ref "U5") (pin "16") (pinfunction "A_16") (pintype "passive+no_connect"))
    )
    (net (code "76") (name "unconnected-(U5-B-Pad15)") (class "Default")
      (node (ref "U5") (pin "15") (pinfunction "B_15") (pintype "passive+no_connect"))
    )
    (net (code "77") (name "unconnected-(U5-ERROR-Pad13)") (class "Default")
      (node (ref "U5") (pin "13") (pinfunction "ERROR_13") (pintype "passive"))
    )
    (net (code "78") (name "unconnected-(U5-OUT-Pad10)") (class "Default")
      (node (ref "U5") (pin "10") (pinfunction "OUT_10") (pintype "passive+no_connect"))
    )
    (net (code "79") (name "unconnected-(U5-U-Pad1)") (class "Default")
      (node (ref "U5") (pin "1") (pinfunction "U_1") (pintype "passive+no_connect"))
    )
    (net (code "80") (name "unconnected-(U5-V-Pad2)") (class "Default")
      (node (ref "U5") (pin "2") (pinfunction "V_2") (pintype "passive+no_connect"))
    )
    (net (code "81") (name "unconnected-(U5-W-Pad3)") (class "Default")
      (node (ref "U5") (pin "3") (pinfunction "W_3") (pintype "passive+no_connect"))
    )
    (net (code "82") (name "unconnected-(U5-Z-Pad14)") (class "Default")
      (node (ref "U5") (pin "14") (pinfunction "Z_14") (pintype "passive+no_connect"))
    )
    (net (code "83") (name "unconnected-(U6-PG-Pad8)") (class "Default")
      (node (ref "U6") (pin "8") (pinfunction "PG_8") (pintype "passive+no_connect"))
    )
  )
)
